# sap_flux-v20.net
KiCad netlist of a schematic drawn in EAGLE
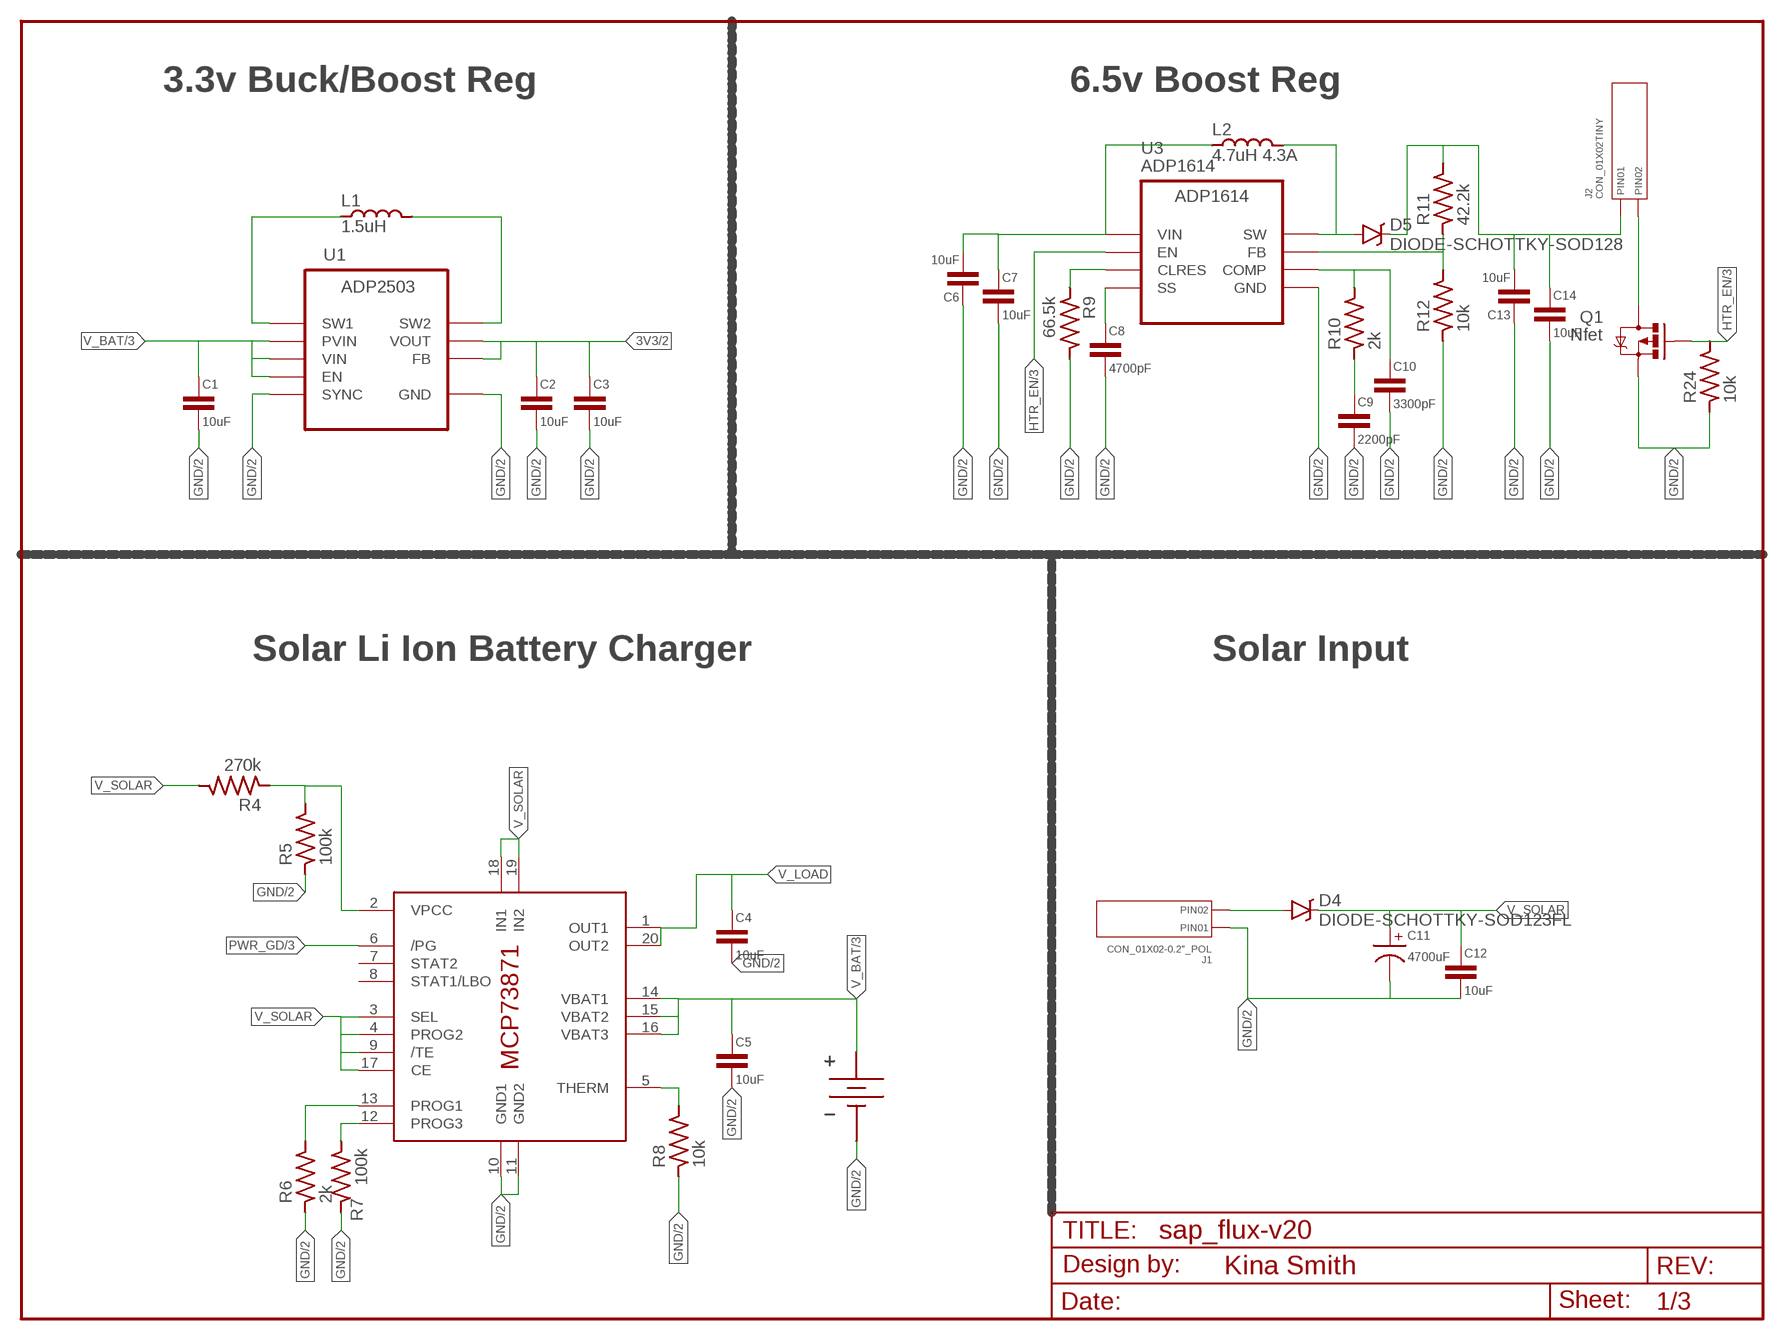
[diagram p0: schematic, sheet 1]
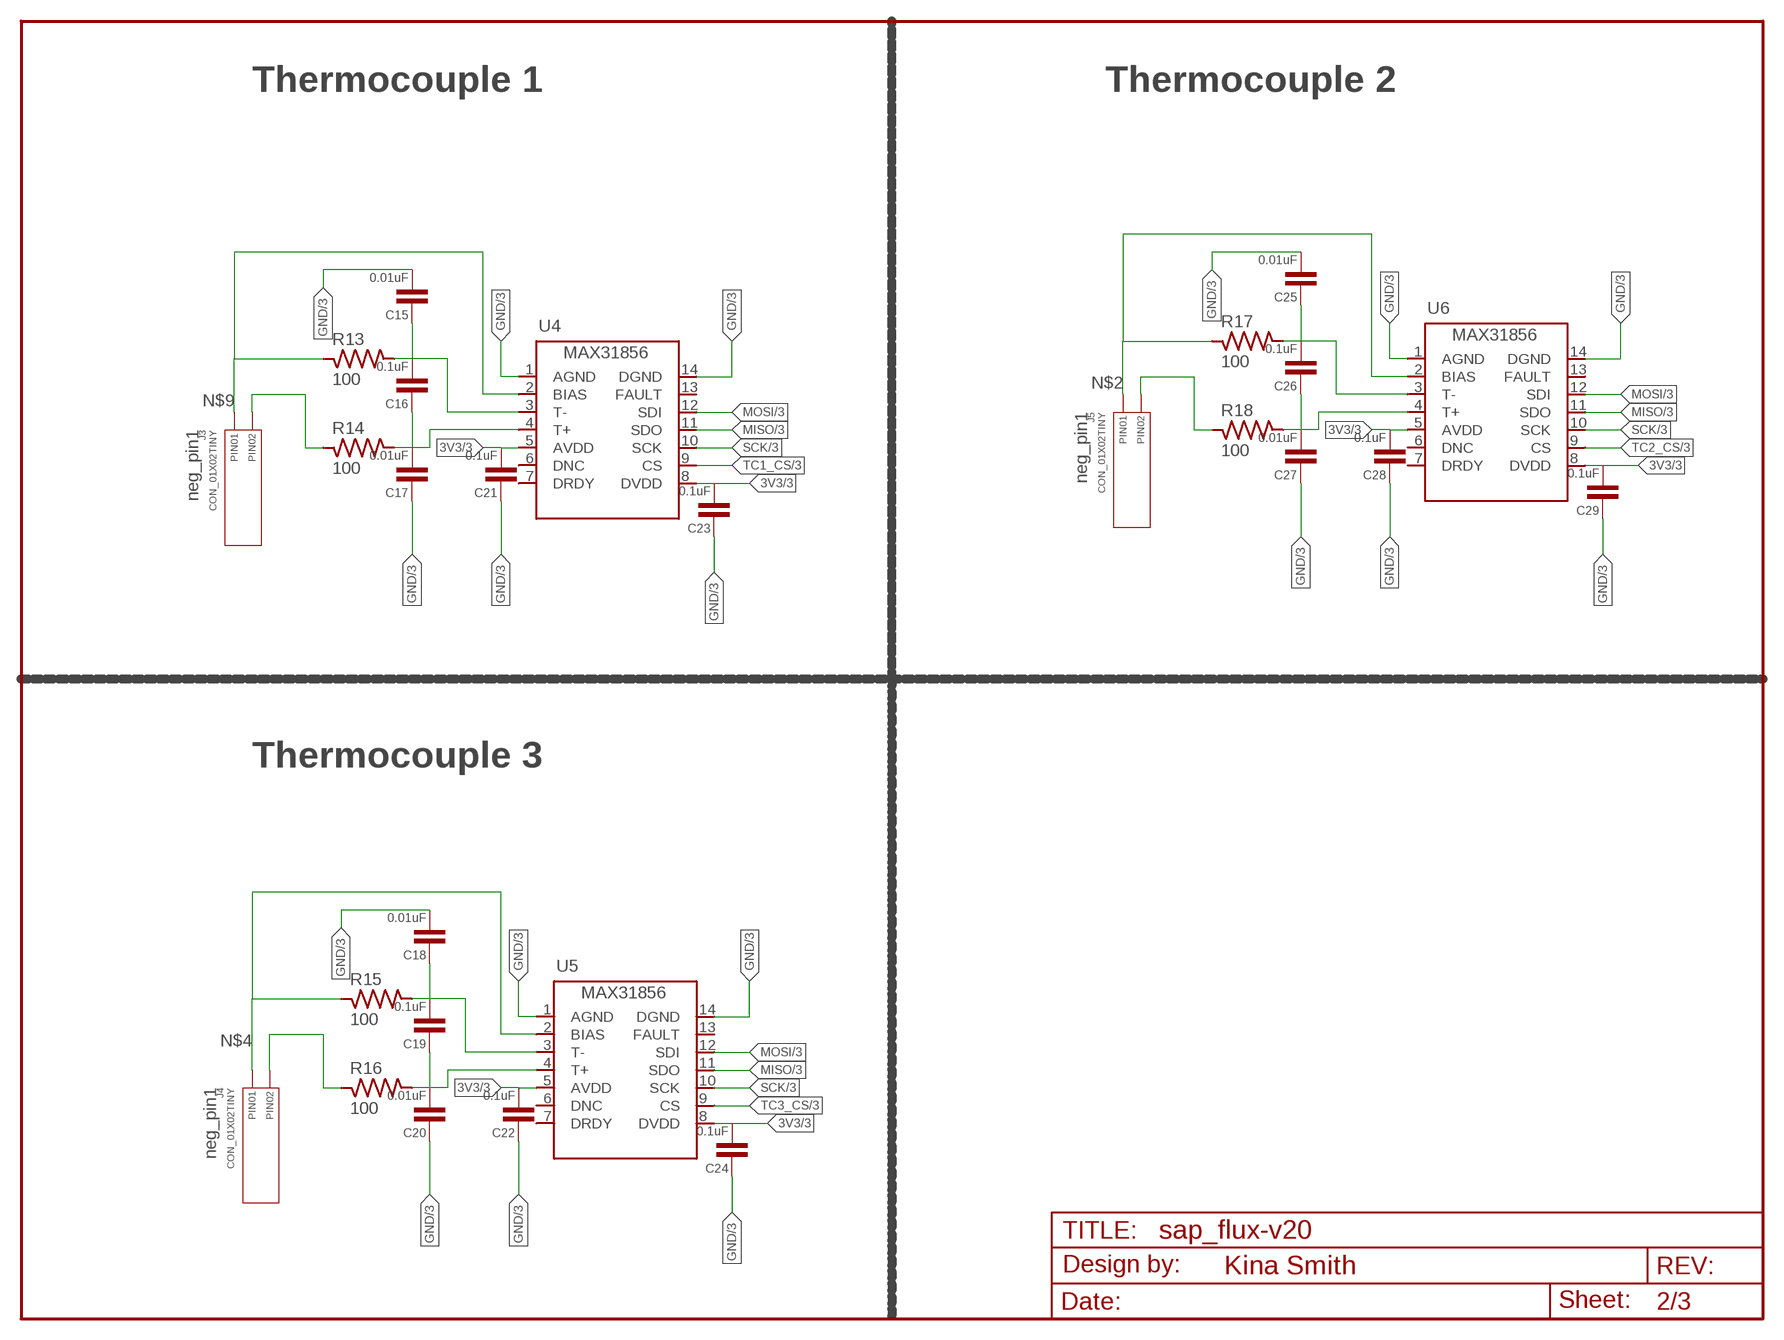
[diagram p1: schematic, sheet 2]
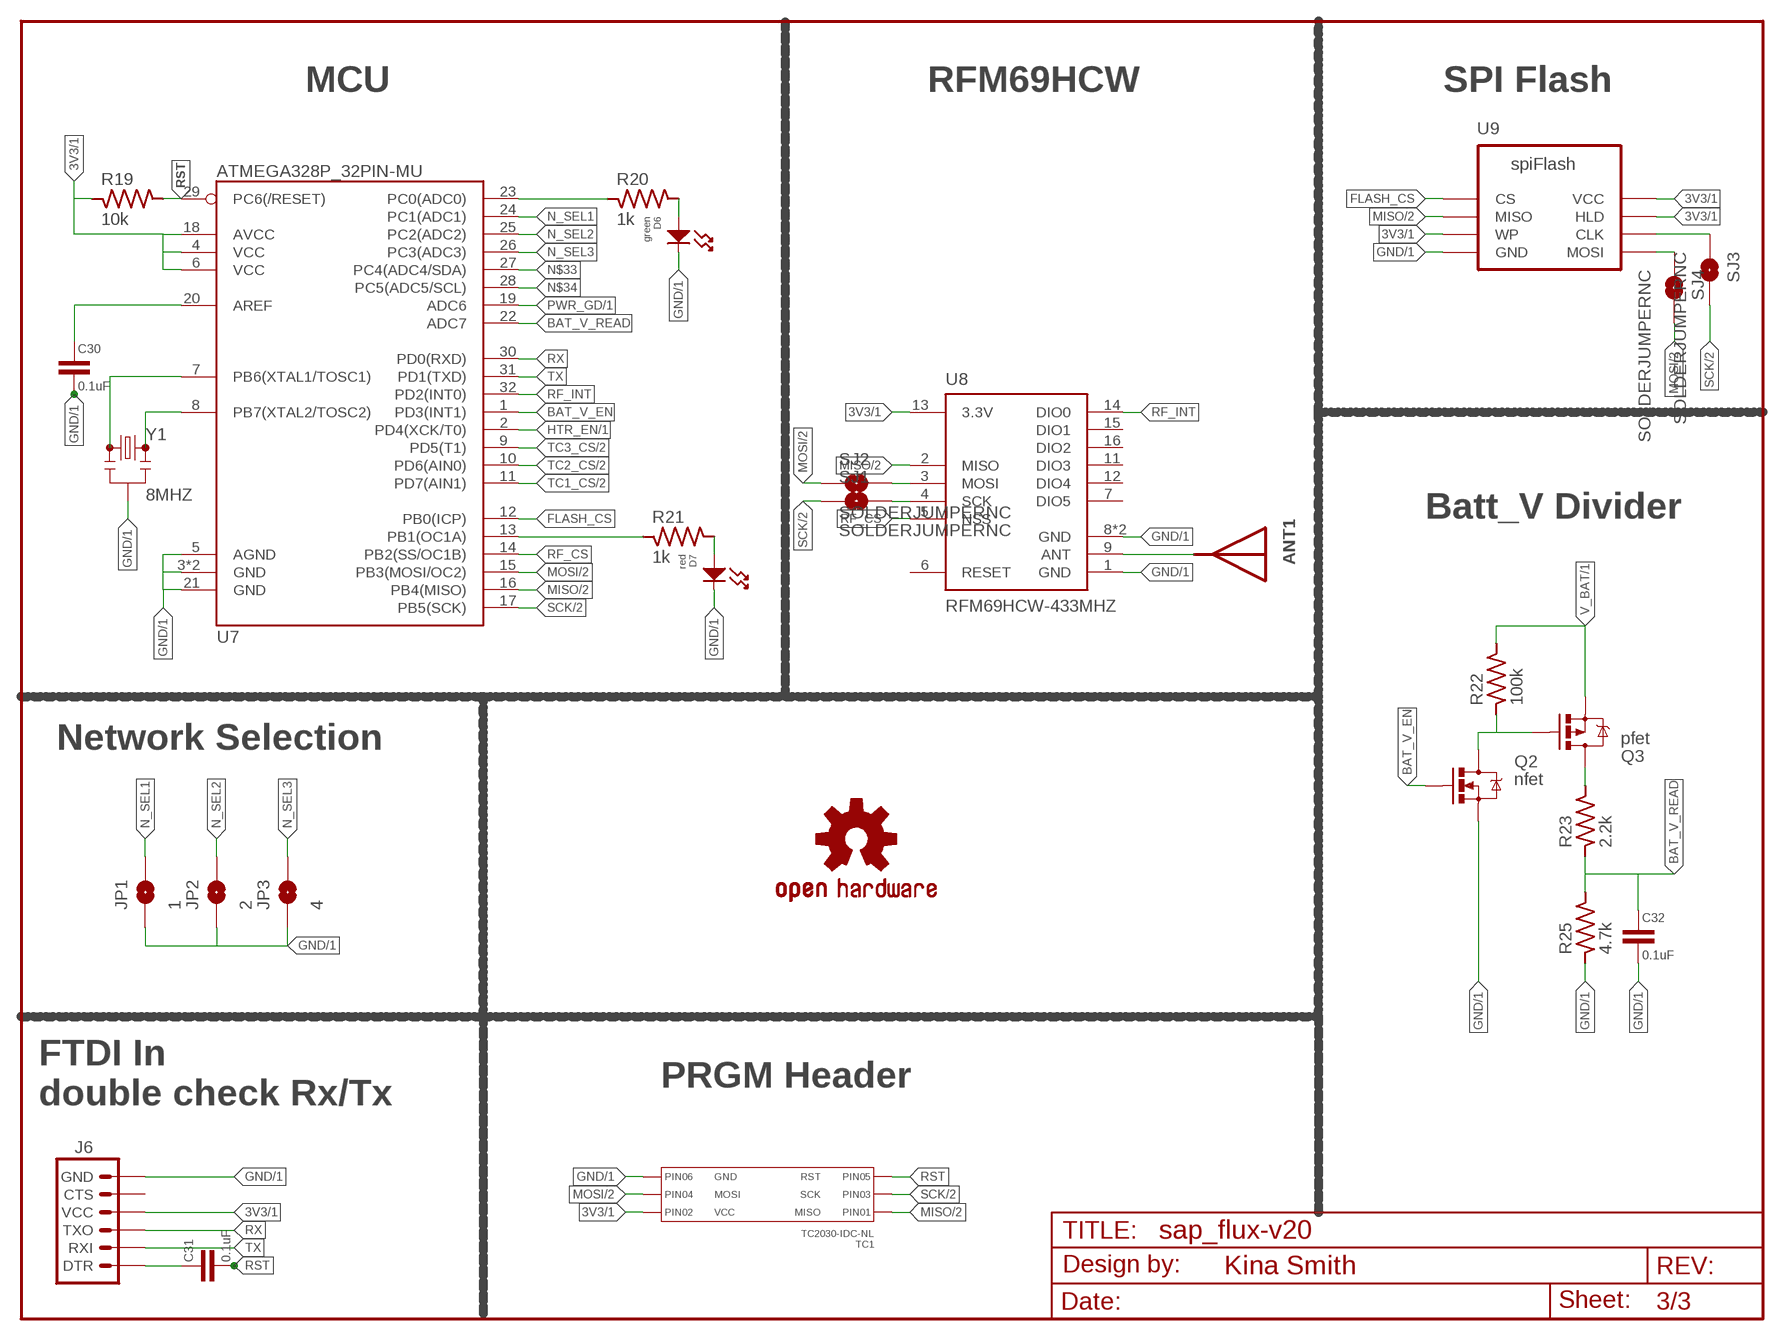
[diagram p2: schematic, sheet 3]

(export (version "E")
  (design (tool "Eeschema 10.0.6"))
  (components
    (comp (ref "ANT1")
      (value "ANTENNA-433_CHIP")
      (footprint "eagle-import:ANT_433_CHIP")
      (fields (field (name "PARTNO") "0433AT62A0020E"))
      (libsource (lib "eagle-import") (part "ANTENNA-433_CHIP"))
    )
    (comp (ref "C30")
      (value "0.1uF")
      (footprint "eagle-import:C0603-N")
      (fields (field (name "PARTNO") "CC0603KRX7R7BB104"))
      (libsource (lib "eagle-import") (part "CAPACITOR_NP0603-N"))
    )
    (comp (ref "C31")
      (value "0.1uF")
      (footprint "eagle-import:C0603-N")
      (fields (field (name "PARTNO") "CC0603KRX7R7BB104"))
      (libsource (lib "eagle-import") (part "CAPACITOR_NP0603-N"))
    )
    (comp (ref "C32")
      (value "0.1uF")
      (footprint "eagle-import:C0603-N")
      (fields (field (name "PARTNO") "CC0603KRX7R7BB104"))
      (libsource (lib "eagle-import") (part "CAPACITOR_NP0603-N"))
    )
    (comp (ref "D6")
      (value "green")
      (footprint "eagle-import:LED0603")
      (fields (field (name "HOUSEPART") "NO") (field (name "PARTNO") "LTST-C191KGKT"))
      (libsource (lib "eagle-import") (part "LED_SINGLE-0603"))
    )
    (comp (ref "D7")
      (value "red")
      (footprint "eagle-import:LED0603")
      (fields (field (name "HOUSEPART") "NO") (field (name "PARTNO") "LTST-C191KRKT"))
      (libsource (lib "eagle-import") (part "LED_SINGLE-0603"))
    )
    (comp (ref "FRAME3")
      (value "FRAME-LETTERNO_PACKAGE")
      (footprint "eagle-import:DUMMY")
      (fields (field (name "PARTNO") "NA") (field (name "DESIGNER") "Nobody"))
      (libsource (lib "eagle-import") (part "FRAME-LETTERNO_PACKAGE"))
    )
    (comp (ref "J6")
      (value "ARDUINO_SERIAL_PROGRAMPTH")
      (footprint "eagle-import:1X06")
      (fields (field (name "PARTNO") "68001-106HLF"))
      (libsource (lib "eagle-import") (part "ARDUINO_SERIAL_PROGRAMPTH"))
    )
    (comp (ref "JP1")
      (value "1")
      (footprint "eagle-import:PAD-JUMPER-2-NO_YES_SILK")
      (fields (field (name "PARTNO") "NA"))
      (libsource (lib "eagle-import") (part "JUMPER-PAD-2-NOYES_SILK"))
    )
    (comp (ref "JP2")
      (value "2")
      (footprint "eagle-import:PAD-JUMPER-2-NO_YES_SILK")
      (fields (field (name "PARTNO") "NA"))
      (libsource (lib "eagle-import") (part "JUMPER-PAD-2-NOYES_SILK"))
    )
    (comp (ref "JP3")
      (value "4")
      (footprint "eagle-import:PAD-JUMPER-2-NO_YES_SILK")
      (fields (field (name "PARTNO") "NA"))
      (libsource (lib "eagle-import") (part "JUMPER-PAD-2-NOYES_SILK"))
    )
    (comp (ref "LOGO1")
      (value "OSHW-LOGOS-COPPER")
      (footprint "eagle-import:OSHW-LOGO-S_COPPER")
      (libsource (lib "eagle-import") (part "OSHW-LOGOS-COPPER"))
    )
    (comp (ref "Q2")
      (value "nfet")
      (footprint "eagle-import:SOT23-3")
      (fields (field (name "PARTNO") "BSS138"))
      (libsource (lib "eagle-import") (part "MOSFET-NCHANNELSOT23-3"))
    )
    (comp (ref "Q3")
      (value "pfet")
      (footprint "eagle-import:SOT23-3")
      (fields (field (name "PARTNO") "IRLML2244TRPBF"))
      (libsource (lib "eagle-import") (part "MOSFET-PCHANNELSOT23-3"))
    )
    (comp (ref "R19")
      (value "10k")
      (footprint "eagle-import:R0603-N")
      (fields (field (name "PARTNO") "RC0603FR-0710KL"))
      (libsource (lib "eagle-import") (part "RESISTOR0603-N"))
    )
    (comp (ref "R20")
      (value "1k")
      (footprint "eagle-import:R0603-N")
      (fields (field (name "PARTNO") "RC0603FR-071KL"))
      (libsource (lib "eagle-import") (part "RESISTOR0603-N"))
    )
    (comp (ref "R21")
      (value "1k")
      (footprint "eagle-import:R0603-N")
      (fields (field (name "PARTNO") "RC0603FR-071KL"))
      (libsource (lib "eagle-import") (part "RESISTOR0603-N"))
    )
    (comp (ref "R22")
      (value "100k")
      (footprint "eagle-import:R0603-N")
      (fields (field (name "PARTNO") "RC0603FR-07100KL"))
      (libsource (lib "eagle-import") (part "RESISTOR0603-N"))
    )
    (comp (ref "R23")
      (value "2.2k")
      (footprint "eagle-import:R0603-N")
      (fields (field (name "PARTNO") "RC0603FR-072K2L"))
      (libsource (lib "eagle-import") (part "RESISTOR0603-N"))
    )
    (comp (ref "R25")
      (value "4.7k")
      (footprint "eagle-import:R0603-N")
      (fields (field (name "PARTNO") "RC0603FR-074K7L"))
      (libsource (lib "eagle-import") (part "RESISTOR0603-N"))
    )
    (comp (ref "SJ1")
      (value "SOLDERJUMPERNC")
      (footprint "eagle-import:SJ_2S")
      (fields (field (name "PARTNO") "NA"))
      (libsource (lib "eagle-import") (part "SOLDERJUMPERNC"))
    )
    (comp (ref "SJ2")
      (value "SOLDERJUMPERNC")
      (footprint "eagle-import:SJ_2S")
      (fields (field (name "PARTNO") "NA"))
      (libsource (lib "eagle-import") (part "SOLDERJUMPERNC"))
    )
    (comp (ref "SJ3")
      (value "SOLDERJUMPERNC")
      (footprint "eagle-import:SJ_2S")
      (fields (field (name "PARTNO") "NA"))
      (libsource (lib "eagle-import") (part "SOLDERJUMPERNC"))
    )
    (comp (ref "SJ4")
      (value "SOLDERJUMPERNC")
      (footprint "eagle-import:SJ_2S")
      (fields (field (name "PARTNO") "NA"))
      (libsource (lib "eagle-import") (part "SOLDERJUMPERNC"))
    )
    (comp (ref "TC1")
      (value "TC2030-IDC-NL")
      (footprint "eagle-import:TC2030-IDC-NL")
      (fields (field (name "HOUSEPART") "NO") (field (name "PARTNO") "NA"))
      (libsource (lib "eagle-import") (part "CON_02X03_TC2030-IDC-NL_AVRISP"))
    )
    (comp (ref "U7")
      (value "ATMEGA328P_32PIN-MU")
      (footprint "eagle-import:MLF32_RECTPADS")
      (fields (field (name "PARTNO") "ATMEGA328P-MU"))
      (libsource (lib "eagle-import") (part "ATMEGA328P_32PIN-MU"))
    )
    (comp (ref "U8")
      (value "RFM69HCW-433MHZ")
      (footprint "eagle-import:RFM69HCW-XXXS2")
      (fields (field (name "PARTNO") "COM-13910"))
      (libsource (lib "eagle-import") (part "RFM69HCW-433MHZ"))
    )
    (comp (ref "U9")
      (value "WINBOND_FLASH_4MBIT-SOIC")
      (footprint "eagle-import:SOIC8")
      (fields (field (name "PARTNO") "W25X40CLSNIG"))
      (libsource (lib "eagle-import") (part "WINBOND_FLASH_4MBIT-SOIC"))
    )
    (comp (ref "Y1")
      (value "8MHZ")
      (footprint "eagle-import:RESONATOR-SMD")
      (fields (field (name "PARTNO") "CSTCE8M00G55-R0"))
      (libsource (lib "eagle-import") (part "RESONATOR8MHZ"))
    )
    (comp (ref "BATT1")
      (value "BATTERY_HOLDER-18650_CLIP")
      (footprint "eagle-import:BAT_18650_CLIP")
      (fields (field (name "PARTNO") "54"))
      (libsource (lib "eagle-import") (part "BATTERY_HOLDER-18650_CLIP"))
    )
    (comp (ref "C1")
      (value "10uF")
      (footprint "eagle-import:C0805-N")
      (fields (field (name "PARTNO") "GRM21BR61C106KE15K"))
      (libsource (lib "eagle-import") (part "CAPACITOR_NP0805-N"))
    )
    (comp (ref "C2")
      (value "10uF")
      (footprint "eagle-import:C0805-N")
      (fields (field (name "PARTNO") "GRM21BR61C106KE15K"))
      (libsource (lib "eagle-import") (part "CAPACITOR_NP0805-N"))
    )
    (comp (ref "C3")
      (value "10uF")
      (footprint "eagle-import:C0805-N")
      (fields (field (name "PARTNO") "GRM21BR61C106KE15K"))
      (libsource (lib "eagle-import") (part "CAPACITOR_NP0805-N"))
    )
    (comp (ref "C4")
      (value "10uF")
      (footprint "eagle-import:C0805-N")
      (fields (field (name "PARTNO") "GRM21BR61C106KE15K"))
      (libsource (lib "eagle-import") (part "CAPACITOR_NP0805-N"))
    )
    (comp (ref "C5")
      (value "10uF")
      (footprint "eagle-import:C0805-N")
      (fields (field (name "PARTNO") "GRM21BR61C106KE15K"))
      (libsource (lib "eagle-import") (part "CAPACITOR_NP0805-N"))
    )
    (comp (ref "C6")
      (value "10uF")
      (footprint "eagle-import:C0805-N")
      (fields (field (name "PARTNO") "GRM21BR61C106KE15K"))
      (libsource (lib "eagle-import") (part "CAPACITOR_NP0805-N"))
    )
    (comp (ref "C7")
      (value "10uF")
      (footprint "eagle-import:C0805-N")
      (fields (field (name "PARTNO") "GRM21BR61C106KE15K"))
      (libsource (lib "eagle-import") (part "CAPACITOR_NP0805-N"))
    )
    (comp (ref "C8")
      (value "4700pF")
      (footprint "eagle-import:C0603-N")
      (fields (field (name "PARTNO") "GRM188R71C472KA01D"))
      (libsource (lib "eagle-import") (part "CAPACITOR_NP0603-N"))
    )
    (comp (ref "C9")
      (value "2200pF")
      (footprint "eagle-import:C0603-N")
      (fields (field (name "PARTNO") "GRM188R71C222KA01D"))
      (libsource (lib "eagle-import") (part "CAPACITOR_NP0603-N"))
    )
    (comp (ref "C10")
      (value "3300pF")
      (footprint "eagle-import:C0603-N")
      (fields (field (name "PARTNO") "C0603C332K4RACTU"))
      (libsource (lib "eagle-import") (part "CAPACITOR_NP0603-N"))
    )
    (comp (ref "C11")
      (value "4700uF")
      (footprint "eagle-import:CP_TH_5MM")
      (fields (field (name "PARTNO") "ECA-1AM472"))
      (libsource (lib "eagle-import") (part "CAPACITOR_P-TH_5MM"))
    )
    (comp (ref "C12")
      (value "10uF")
      (footprint "eagle-import:C0805-N")
      (fields (field (name "PARTNO") "GRM21BR61C106KE15K"))
      (libsource (lib "eagle-import") (part "CAPACITOR_NP0805-N"))
    )
    (comp (ref "C13")
      (value "10uF")
      (footprint "eagle-import:C0805-N")
      (fields (field (name "PARTNO") "GRM21BR61C106KE15K"))
      (libsource (lib "eagle-import") (part "CAPACITOR_NP0805-N"))
    )
    (comp (ref "C14")
      (value "10uF")
      (footprint "eagle-import:C0805-N")
      (fields (field (name "PARTNO") "GRM21BR61C106KE15K"))
      (libsource (lib "eagle-import") (part "CAPACITOR_NP0805-N"))
    )
    (comp (ref "D4")
      (value "DIODE-SCHOTTKY-SOD123FL")
      (footprint "eagle-import:SOD-123FL")
      (fields (field (name "PARTNO") "MBR120VLSFT1G"))
      (libsource (lib "eagle-import") (part "DIODE-SCHOTTKY-SOD123FL"))
    )
    (comp (ref "D5")
      (value "DIODE-SCHOTTKY-SOD128")
      (footprint "eagle-import:SOD128")
      (fields (field (name "PARTNO") "CMS05(TE12L,Q,M)"))
      (libsource (lib "eagle-import") (part "DIODE-SCHOTTKY-SOD128"))
    )
    (comp (ref "FRAME1")
      (value "FRAME-LETTER")
      (footprint "eagle-import:CREATIVE_COMMONS")
      (fields (field (name "PARTNO") "NA"))
      (libsource (lib "eagle-import") (part "FRAME-LETTER"))
    )
    (comp (ref "J1")
      (value "CON_01X02-0.2\"_POL")
      (footprint "eagle-import:1X02_SCREWTERM_0.2IN")
      (fields (field (name "PARTNO") "0398890042"))
      (libsource (lib "eagle-import") (part "CON_01X02-0.2{dblquote}_POL"))
    )
    (comp (ref "J2")
      (value "CON_01X02TINY")
      (footprint "eagle-import:1X02_TINY")
      (libsource (lib "eagle-import") (part "CON_01X02TINY"))
    )
    (comp (ref "L1")
      (value "1.5uH")
      (footprint "eagle-import:L3030")
      (fields (field (name "PARTNO") "NR3015T1R5N"))
      (libsource (lib "eagle-import") (part "INDUCTOR3030"))
    )
    (comp (ref "L2")
      (value "4.7uH 4.3A")
      (footprint "eagle-import:L8080")
      (fields (field (name "PARTNO") "NRS8040T100MJGJ"))
      (libsource (lib "eagle-import") (part "INDUCTOR8080"))
    )
    (comp (ref "Q1")
      (value "Nfet")
      (footprint "eagle-import:SOT23-3")
      (fields (field (name "PARTNO") "DMN2075U-7"))
      (libsource (lib "eagle-import") (part "MOSFET-PCHANNELSOT23-3"))
    )
    (comp (ref "R4")
      (value "270k")
      (footprint "eagle-import:R0603-N")
      (fields (field (name "PARTNO") "RC0603FR-07270KL"))
      (libsource (lib "eagle-import") (part "RESISTOR0603-N"))
    )
    (comp (ref "R5")
      (value "100k")
      (footprint "eagle-import:R0603-N")
      (fields (field (name "PARTNO") "RC0603FR-07100KL"))
      (libsource (lib "eagle-import") (part "RESISTOR0603-N"))
    )
    (comp (ref "R6")
      (value "2k")
      (footprint "eagle-import:R0603-N")
      (fields (field (name "PARTNO") "RC0603FR-072KL"))
      (libsource (lib "eagle-import") (part "RESISTOR0603-N"))
    )
    (comp (ref "R7")
      (value "100k")
      (footprint "eagle-import:R0603-N")
      (fields (field (name "PARTNO") "RC0603FR-07100KL"))
      (libsource (lib "eagle-import") (part "RESISTOR0603-N"))
    )
    (comp (ref "R8")
      (value "10k")
      (footprint "eagle-import:R0603-N")
      (fields (field (name "PARTNO") "RC0603FR-0710KL"))
      (libsource (lib "eagle-import") (part "RESISTOR0603-N"))
    )
    (comp (ref "R9")
      (value "66.5k")
      (footprint "eagle-import:R0603-N")
      (fields (field (name "PARTNO") "RC0603FR-0766K5L"))
      (libsource (lib "eagle-import") (part "RESISTOR0603-N"))
    )
    (comp (ref "R10")
      (value "2k")
      (footprint "eagle-import:R0603-N")
      (fields (field (name "PARTNO") "RC0603FR-072KL"))
      (libsource (lib "eagle-import") (part "RESISTOR0603-N"))
    )
    (comp (ref "R11")
      (value "42.2k")
      (footprint "eagle-import:R0603-N")
      (fields (field (name "PARTNO") "RC0603FR-0742K2L"))
      (libsource (lib "eagle-import") (part "RESISTOR0603-N"))
    )
    (comp (ref "R12")
      (value "10k")
      (footprint "eagle-import:R0603-N")
      (fields (field (name "PARTNO") "RC0603FR-0710KL"))
      (libsource (lib "eagle-import") (part "RESISTOR0603-N"))
    )
    (comp (ref "R24")
      (value "10k")
      (footprint "eagle-import:R0603-N")
      (fields (field (name "PARTNO") "RC0603FR-0710KL"))
      (libsource (lib "eagle-import") (part "RESISTOR0603-N"))
    )
    (comp (ref "U1")
      (value "ADP2503")
      (footprint "eagle-import:DFN300X300X80-11N")
      (fields (field (name "PARTNO") "ADP2503ACPZ-3.3-R7 ") (field (name "PARTNO_1") "ADP2503ACPZ-3.3-R7"))
      (libsource (lib "eagle-import") (part "ADP2503"))
    )
    (comp (ref "U2")
      (value "MCP73871")
      (footprint "eagle-import:QFN20")
      (fields (field (name "PARTNO") "MCP73871-2AAI/ML-ND"))
      (libsource (lib "eagle-import") (part "MCP73871"))
    )
    (comp (ref "U3")
      (value "ADP1614")
      (footprint "eagle-import:DFN300X300X80-11N")
      (fields (field (name "PARTNO") "ADP1614ACPZ-R7") (field (name "PARTNO_1") "ADP1614ACPZ-650-R7"))
      (libsource (lib "eagle-import") (part "ADP1614"))
    )
    (comp (ref "C15")
      (value "0.01uF")
      (footprint "eagle-import:C0603-N")
      (fields (field (name "PARTNO") "GRM188R71C103KA01D"))
      (libsource (lib "eagle-import") (part "CAPACITOR_NP0603-N"))
    )
    (comp (ref "C16")
      (value "0.1uF")
      (footprint "eagle-import:C0603-N")
      (fields (field (name "PARTNO") "CC0603KRX7R7BB104"))
      (libsource (lib "eagle-import") (part "CAPACITOR_NP0603-N"))
    )
    (comp (ref "C17")
      (value "0.01uF")
      (footprint "eagle-import:C0603-N")
      (fields (field (name "PARTNO") "GRM188R71C103KA01D"))
      (libsource (lib "eagle-import") (part "CAPACITOR_NP0603-N"))
    )
    (comp (ref "C18")
      (value "0.01uF")
      (footprint "eagle-import:C0603-N")
      (fields (field (name "PARTNO") "GRM188R71C103KA01D"))
      (libsource (lib "eagle-import") (part "CAPACITOR_NP0603-N"))
    )
    (comp (ref "C19")
      (value "0.1uF")
      (footprint "eagle-import:C0603-N")
      (fields (field (name "PARTNO") "CC0603KRX7R7BB104"))
      (libsource (lib "eagle-import") (part "CAPACITOR_NP0603-N"))
    )
    (comp (ref "C20")
      (value "0.01uF")
      (footprint "eagle-import:C0603-N")
      (fields (field (name "PARTNO") "GRM188R71C103KA01D"))
      (libsource (lib "eagle-import") (part "CAPACITOR_NP0603-N"))
    )
    (comp (ref "C21")
      (value "0.1uF")
      (footprint "eagle-import:C0603-N")
      (fields (field (name "PARTNO") "CC0603KRX7R7BB104"))
      (libsource (lib "eagle-import") (part "CAPACITOR_NP0603-N"))
    )
    (comp (ref "C22")
      (value "0.1uF")
      (footprint "eagle-import:C0603-N")
      (fields (field (name "PARTNO") "CC0603KRX7R7BB104"))
      (libsource (lib "eagle-import") (part "CAPACITOR_NP0603-N"))
    )
    (comp (ref "C23")
      (value "0.1uF")
      (footprint "eagle-import:C0603-N")
      (fields (field (name "PARTNO") "CC0603KRX7R7BB104"))
      (libsource (lib "eagle-import") (part "CAPACITOR_NP0603-N"))
    )
    (comp (ref "C24")
      (value "0.1uF")
      (footprint "eagle-import:C0603-N")
      (fields (field (name "PARTNO") "CC0603KRX7R7BB104"))
      (libsource (lib "eagle-import") (part "CAPACITOR_NP0603-N"))
    )
    (comp (ref "C25")
      (value "0.01uF")
      (footprint "eagle-import:C0603-N")
      (fields (field (name "PARTNO") "GRM188R71C103KA01D"))
      (libsource (lib "eagle-import") (part "CAPACITOR_NP0603-N"))
    )
    (comp (ref "C26")
      (value "0.1uF")
      (footprint "eagle-import:C0603-N")
      (fields (field (name "PARTNO") "CC0603KRX7R7BB104"))
      (libsource (lib "eagle-import") (part "CAPACITOR_NP0603-N"))
    )
    (comp (ref "C27")
      (value "0.01uF")
      (footprint "eagle-import:C0603-N")
      (fields (field (name "PARTNO") "GRM188R71C103KA01D"))
      (libsource (lib "eagle-import") (part "CAPACITOR_NP0603-N"))
    )
    (comp (ref "C28")
      (value "0.1uF")
      (footprint "eagle-import:C0603-N")
      (fields (field (name "PARTNO") "CC0603KRX7R7BB104"))
      (libsource (lib "eagle-import") (part "CAPACITOR_NP0603-N"))
    )
    (comp (ref "C29")
      (value "0.1uF")
      (footprint "eagle-import:C0603-N")
      (fields (field (name "PARTNO") "CC0603KRX7R7BB104"))
      (libsource (lib "eagle-import") (part "CAPACITOR_NP0603-N"))
    )
    (comp (ref "FRAME2")
      (value "FRAME-LETTERNO_PACKAGE")
      (footprint "eagle-import:DUMMY")
      (fields (field (name "PARTNO") "NA") (field (name "DESIGNER") "Nobody"))
      (libsource (lib "eagle-import") (part "FRAME-LETTERNO_PACKAGE"))
    )
    (comp (ref "J3")
      (value "CON_01X02TINY")
      (footprint "eagle-import:1X02_TINY")
      (fields (field (name "NOTE") "neg_pin1"))
      (libsource (lib "eagle-import") (part "CON_01X02TINY"))
    )
    (comp (ref "J4")
      (value "CON_01X02TINY")
      (footprint "eagle-import:1X02_TINY")
      (fields (field (name "NOTE") "neg_pin1"))
      (libsource (lib "eagle-import") (part "CON_01X02TINY"))
    )
    (comp (ref "J5")
      (value "CON_01X02TINY")
      (footprint "eagle-import:1X02_TINY")
      (fields (field (name "NOTE") "neg_pin1"))
      (libsource (lib "eagle-import") (part "CON_01X02TINY"))
    )
    (comp (ref "R13")
      (value "100")
      (footprint "eagle-import:R0603-N")
      (fields (field (name "PARTNO") "RC0603FR-07100RL"))
      (libsource (lib "eagle-import") (part "RESISTOR0603-N"))
    )
    (comp (ref "R14")
      (value "100")
      (footprint "eagle-import:R0603-N")
      (fields (field (name "PARTNO") "RC0603FR-07100RL"))
      (libsource (lib "eagle-import") (part "RESISTOR0603-N"))
    )
    (comp (ref "R15")
      (value "100")
      (footprint "eagle-import:R0603-N")
      (fields (field (name "PARTNO") "RC0603FR-07100RL"))
      (libsource (lib "eagle-import") (part "RESISTOR0603-N"))
    )
    (comp (ref "R16")
      (value "100")
      (footprint "eagle-import:R0603-N")
      (fields (field (name "PARTNO") "RC0603FR-07100RL"))
      (libsource (lib "eagle-import") (part "RESISTOR0603-N"))
    )
    (comp (ref "R17")
      (value "100")
      (footprint "eagle-import:R0603-N")
      (fields (field (name "PARTNO") "RC0603FR-07100RL"))
      (libsource (lib "eagle-import") (part "RESISTOR0603-N"))
    )
    (comp (ref "R18")
      (value "100")
      (footprint "eagle-import:R0603-N")
      (fields (field (name "PARTNO") "RC0603FR-07100RL"))
      (libsource (lib "eagle-import") (part "RESISTOR0603-N"))
    )
    (comp (ref "U4")
      (value "MAX31856MUD+")
      (footprint "eagle-import:TSSOP14")
      (libsource (lib "eagle-import") (part "MAX31856MUD+"))
    )
    (comp (ref "U5")
      (value "MAX31856MUD+")
      (footprint "eagle-import:TSSOP14")
      (libsource (lib "eagle-import") (part "MAX31856MUD+"))
    )
    (comp (ref "U6")
      (value "MAX31856MUD+")
      (footprint "eagle-import:TSSOP14")
      (libsource (lib "eagle-import") (part "MAX31856MUD+"))
    )
  )
  (nets
    (net (code "1") (name "3V3") (class "Default")
      (node (ref "C2") (pin "1") (pinfunction "1_1") (pintype "passive"))
      (node (ref "C21") (pin "2") (pinfunction "2_2") (pintype "passive"))
      (node (ref "C22") (pin "2") (pinfunction "2_2") (pintype "passive"))
      (node (ref "C23") (pin "2") (pinfunction "2_2") (pintype "passive"))
      (node (ref "C24") (pin "2") (pinfunction "2_2") (pintype "passive"))
      (node (ref "C28") (pin "2") (pinfunction "2_2") (pintype "passive"))
      (node (ref "C29") (pin "2") (pinfunction "2_2") (pintype "passive"))
      (node (ref "C3") (pin "1") (pinfunction "1_1") (pintype "passive"))
      (node (ref "J6") (pin "4") (pinfunction "VCC_4") (pintype "passive"))
      (node (ref "R19") (pin "1") (pinfunction "P$1_1") (pintype "passive"))
      (node (ref "TC1") (pin "P$2") (pinfunction "PIN2_P$2") (pintype "bidirectional"))
      (node (ref "U1") (pin "1") (pinfunction "VOUT_1") (pintype "bidirectional"))
      (node (ref "U1") (pin "10") (pinfunction "FB_10") (pintype "bidirectional"))
      (node (ref "U4") (pin "5") (pinfunction "AVDD_5") (pintype "bidirectional"))
      (node (ref "U4") (pin "8") (pinfunction "DVDD_8") (pintype "bidirectional"))
      (node (ref "U5") (pin "5") (pinfunction "AVDD_5") (pintype "bidirectional"))
      (node (ref "U5") (pin "8") (pinfunction "DVDD_8") (pintype "bidirectional"))
      (node (ref "U6") (pin "5") (pinfunction "AVDD_5") (pintype "bidirectional"))
      (node (ref "U6") (pin "8") (pinfunction "DVDD_8") (pintype "bidirectional"))
      (node (ref "U7") (pin "18") (pinfunction "AVCC_18") (pintype "bidirectional"))
      (node (ref "U7") (pin "4") (pinfunction "VCC_4") (pintype "bidirectional"))
      (node (ref "U7") (pin "6") (pinfunction "VCC_6") (pintype "bidirectional"))
      (node (ref "U8") (pin "13") (pinfunction "3.3V_13") (pintype "power_in"))
      (node (ref "U9") (pin "3") (pinfunction "WP_3") (pintype "bidirectional"))
      (node (ref "U9") (pin "7") (pinfunction "HLD_7") (pintype "bidirectional"))
      (node (ref "U9") (pin "8") (pinfunction "VCC_8") (pintype "bidirectional"))
    )
    (net (code "2") (name "BAT_V_EN") (class "Default")
      (node (ref "Q2") (pin "1") (pinfunction "G_1") (pintype "passive"))
      (node (ref "U7") (pin "1") (pinfunction "PD3(INT1)_1") (pintype "bidirectional"))
    )
    (net (code "3") (name "BAT_V_READ") (class "Default")
      (node (ref "C32") (pin "1") (pinfunction "1_1") (pintype "passive"))
      (node (ref "R23") (pin "1") (pinfunction "P$1_1") (pintype "passive"))
      (node (ref "R25") (pin "2") (pinfunction "P$2_2") (pintype "passive"))
      (node (ref "U7") (pin "22") (pinfunction "ADC7_22") (pintype "bidirectional"))
    )
    (net (code "4") (name "FLASH_CS") (class "Default")
      (node (ref "U7") (pin "12") (pinfunction "PB0(ICP)_12") (pintype "bidirectional"))
      (node (ref "U9") (pin "1") (pinfunction "CS_1") (pintype "bidirectional"))
    )
    (net (code "5") (name "GND") (class "Default")
      (node (ref "BATT1") (pin "NEG_1") (pinfunction "GND_NEG_1") (pintype "bidirectional"))
      (node (ref "BATT1") (pin "NEG_2") (pinfunction "GND_NEG_2") (pintype "bidirectional"))
      (node (ref "BATT1") (pin "NEG_3") (pinfunction "GND_NEG_3") (pintype "bidirectional"))
      (node (ref "C1") (pin "2") (pinfunction "2_2") (pintype "passive"))
      (node (ref "C10") (pin "2") (pinfunction "2_2") (pintype "passive"))
      (node (ref "C11") (pin "NEG") (pinfunction "NEG_NEG") (pintype "passive"))
      (node (ref "C12") (pin "2") (pinfunction "2_2") (pintype "passive"))
      (node (ref "C13") (pin "1") (pinfunction "1_1") (pintype "passive"))
      (node (ref "C14") (pin "2") (pinfunction "2_2") (pintype "passive"))
      (node (ref "C15") (pin "2") (pinfunction "2_2") (pintype "passive"))
      (node (ref "C17") (pin "1") (pinfunction "1_1") (pintype "passive"))
      (node (ref "C18") (pin "2") (pinfunction "2_2") (pintype "passive"))
      (node (ref "C2") (pin "2") (pinfunction "2_2") (pintype "passive"))
      (node (ref "C20") (pin "1") (pinfunction "1_1") (pintype "passive"))
      (node (ref "C21") (pin "1") (pinfunction "1_1") (pintype "passive"))
      (node (ref "C22") (pin "1") (pinfunction "1_1") (pintype "passive"))
      (node (ref "C23") (pin "1") (pinfunction "1_1") (pintype "passive"))
      (node (ref "C24") (pin "1") (pinfunction "1_1") (pintype "passive"))
      (node (ref "C25") (pin "2") (pinfunction "2_2") (pintype "passive"))
      (node (ref "C27") (pin "1") (pinfunction "1_1") (pintype "passive"))
      (node (ref "C28") (pin "1") (pinfunction "1_1") (pintype "passive"))
      (node (ref "C29") (pin "1") (pinfunction "1_1") (pintype "passive"))
      (node (ref "C3") (pin "2") (pinfunction "2_2") (pintype "passive"))
      (node (ref "C30") (pin "2") (pinfunction "2_2") (pintype "passive"))
      (node (ref "C32") (pin "2") (pinfunction "2_2") (pintype "passive"))
      (node (ref "C4") (pin "2") (pinfunction "2_2") (pintype "passive"))
      (node (ref "C5") (pin "2") (pinfunction "2_2") (pintype "passive"))
      (node (ref "C6") (pin "1") (pinfunction "1_1") (pintype "passive"))
      (node (ref "C7") (pin "2") (pinfunction "2_2") (pintype "passive"))
      (node (ref "C8") (pin "2") (pinfunction "2_2") (pintype "passive"))
      (node (ref "C9") (pin "2") (pinfunction "2_2") (pintype "passive"))
      (node (ref "D6") (pin "CATHODE") (pinfunction "CATHODE_CATHODE") (pintype "power_in"))
      (node (ref "D7") (pin "CATHODE") (pinfunction "CATHODE_CATHODE") (pintype "power_in"))
      (node (ref "J1") (pin "NEG") (pinfunction "PIN1_NEG") (pintype "bidirectional"))
      (node (ref "J6") (pin "6") (pinfunction "GND_6") (pintype "passive"))
      (node (ref "JP1") (pin "1") (pinfunction "1_1") (pintype "passive"))
      (node (ref "JP2") (pin "1") (pinfunction "1_1") (pintype "passive"))
      (node (ref "JP3") (pin "1") (pinfunction "1_1") (pintype "passive"))
      (node (ref "Q1") (pin "2") (pinfunction "S_2") (pintype "passive"))
      (node (ref "Q2") (pin "2") (pinfunction "S_2") (pintype "passive"))
      (node (ref "R12") (pin "1") (pinfunction "P$1_1") (pintype "passive"))
      (node (ref "R24") (pin "1") (pinfunction "P$1_1") (pintype "passive"))
      (node (ref "R25") (pin "1") (pinfunction "P$1_1") (pintype "passive"))
      (node (ref "R5") (pin "1") (pinfunction "P$1_1") (pintype "passive"))
      (node (ref "R6") (pin "1") (pinfunction "P$1_1") (pintype "passive"))
      (node (ref "R7") (pin "1") (pinfunction "P$1_1") (pintype "passive"))
      (node (ref "R8") (pin "1") (pinfunction "P$1_1") (pintype "passive"))
      (node (ref "R9") (pin "2") (pinfunction "P$2_2") (pintype "passive"))
      (node (ref "TC1") (pin "P$6") (pinfunction "PIN6_P$6") (pintype "bidirectional"))
      (node (ref "U1") (pin "11") (pinfunction "GND_11") (pintype "bidirectional"))
      (node (ref "U1") (pin "3") (pinfunction "GND_3") (pintype "bidirectional"))
      (node (ref "U1") (pin "7") (pinfunction "SYNC_7") (pintype "bidirectional"))
      (node (ref "U1") (pin "9") (pinfunction "GND_9") (pintype "bidirectional"))
      (node (ref "U2") (pin "10") (pinfunction "GND1_10") (pintype "power_in"))
      (node (ref "U2") (pin "11") (pinfunction "GND2_11") (pintype "power_in"))
      (node (ref "U3") (pin "11") (pinfunction "GND_11") (pintype "bidirectional"))
      (node (ref "U3") (pin "4") (pinfunction "GND_4") (pintype "bidirectional"))
      (node (ref "U3") (pin "5") (pinfunction "GND_5") (pintype "bidirectional"))
      (node (ref "U4") (pin "1") (pinfunction "AGND_1") (pintype "bidirectional"))
      (node (ref "U4") (pin "14") (pinfunction "DGND_14") (pintype "bidirectional"))
      (node (ref "U5") (pin "1") (pinfunction "AGND_1") (pintype "bidirectional"))
      (node (ref "U5") (pin "14") (pinfunction "DGND_14") (pintype "bidirectional"))
      (node (ref "U6") (pin "1") (pinfunction "AGND_1") (pintype "bidirectional"))
      (node (ref "U6") (pin "14") (pinfunction "DGND_14") (pintype "bidirectional"))
      (node (ref "U7") (pin "21") (pinfunction "GND_21") (pintype "bidirectional"))
      (node (ref "U7") (pin "3") (pinfunction "GND_3") (pintype "bidirectional"))
      (node (ref "U7") (pin "5") (pinfunction "AGND_5") (pintype "bidirectional"))
      (node (ref "U7") (pin "PAD") (pinfunction "GND_PAD") (pintype "bidirectional"))
      (node (ref "U8") (pin "1") (pinfunction "GND_1") (pintype "power_in"))
      (node (ref "U8") (pin "10") (pinfunction "GND_10") (pintype "power_in"))
      (node (ref "U8") (pin "8") (pinfunction "GND_8") (pintype "power_in"))
      (node (ref "U9") (pin "4") (pinfunction "GND_4") (pintype "bidirectional"))
      (node (ref "Y1") (pin "2") (pinfunction "2_2") (pintype "passive"))
    )
    (net (code "6") (name "HTR_EN") (class "Default")
      (node (ref "Q1") (pin "1") (pinfunction "G_1") (pintype "passive"))
      (node (ref "R24") (pin "2") (pinfunction "P$2_2") (pintype "passive"))
      (node (ref "U3") (pin "3") (pinfunction "EN_3") (pintype "bidirectional"))
      (node (ref "U7") (pin "2") (pinfunction "PD4(XCK/T0)_2") (pintype "bidirectional"))
    )
    (net (code "7") (name "MISO") (class "Default")
      (node (ref "TC1") (pin "P$1") (pinfunction "PIN1_P$1") (pintype "bidirectional"))
      (node (ref "U4") (pin "11") (pinfunction "SDO_11") (pintype "bidirectional"))
      (node (ref "U5") (pin "11") (pinfunction "SDO_11") (pintype "bidirectional"))
      (node (ref "U6") (pin "11") (pinfunction "SDO_11") (pintype "bidirectional"))
      (node (ref "U7") (pin "16") (pinfunction "PB4(MISO)_16") (pintype "bidirectional"))
      (node (ref "U8") (pin "2") (pinfunction "MISO_2") (pintype "bidirectional"))
      (node (ref "U9") (pin "2") (pinfunction "MISO_2") (pintype "bidirectional"))
    )
    (net (code "8") (name "MOSI") (class "Default")
      (node (ref "SJ2") (pin "1") (pinfunction "1_1") (pintype "passive"))
      (node (ref "SJ4") (pin "2") (pinfunction "2_2") (pintype "passive"))
      (node (ref "TC1") (pin "P$4") (pinfunction "PIN4_P$4") (pintype "bidirectional"))
      (node (ref "U4") (pin "12") (pinfunction "SDI_12") (pintype "bidirectional"))
      (node (ref "U5") (pin "12") (pinfunction "SDI_12") (pintype "bidirectional"))
      (node (ref "U6") (pin "12") (pinfunction "SDI_12") (pintype "bidirectional"))
      (node (ref "U7") (pin "15") (pinfunction "PB3(MOSI/OC2)_15") (pintype "bidirectional"))
    )
    (net (code "9") (name "N$2") (class "Default")
      (node (ref "J5") (pin "NEG") (pinfunction "PIN1_NEG") (pintype "bidirectional"))
      (node (ref "R17") (pin "1") (pinfunction "P$1_1") (pintype "passive"))
      (node (ref "U6") (pin "2") (pinfunction "BIAS_2") (pintype "bidirectional"))
    )
    (net (code "10") (name "N$4") (class "Default")
      (node (ref "J4") (pin "NEG") (pinfunction "PIN1_NEG") (pintype "bidirectional"))
      (node (ref "R15") (pin "1") (pinfunction "P$1_1") (pintype "passive"))
      (node (ref "U5") (pin "2") (pinfunction "BIAS_2") (pintype "bidirectional"))
    )
    (net (code "11") (name "N$9") (class "Default")
      (node (ref "J3") (pin "NEG") (pinfunction "PIN1_NEG") (pintype "bidirectional"))
      (node (ref "R13") (pin "1") (pinfunction "P$1_1") (pintype "passive"))
      (node (ref "U4") (pin "2") (pinfunction "BIAS_2") (pintype "bidirectional"))
    )
    (net (code "12") (name "N$33") (class "Default")
      (node (ref "U7") (pin "27") (pinfunction "PC4(ADC4/SDA)_27") (pintype "bidirectional"))
    )
    (net (code "13") (name "N$34") (class "Default")
      (node (ref "U7") (pin "28") (pinfunction "PC5(ADC5/SCL)_28") (pintype "bidirectional"))
    )
    (net (code "14") (name "N_SEL1") (class "Default")
      (node (ref "JP1") (pin "2") (pinfunction "2_2") (pintype "passive"))
      (node (ref "U7") (pin "24") (pinfunction "PC1(ADC1)_24") (pintype "bidirectional"))
    )
    (net (code "15") (name "N_SEL2") (class "Default")
      (node (ref "JP2") (pin "2") (pinfunction "2_2") (pintype "passive"))
      (node (ref "U7") (pin "25") (pinfunction "PC2(ADC2)_25") (pintype "bidirectional"))
    )
    (net (code "16") (name "N_SEL3") (class "Default")
      (node (ref "JP3") (pin "2") (pinfunction "2_2") (pintype "passive"))
      (node (ref "U7") (pin "26") (pinfunction "PC3(ADC3)_26") (pintype "bidirectional"))
    )
    (net (code "17") (name "Net-(D5-A)") (class "Default")
      (node (ref "D5") (pin "A-2") (pinfunction "A_A-2") (pintype "passive"))
      (node (ref "L2") (pin "2") (pinfunction "P$2_2") (pintype "passive"))
      (node (ref "U3") (pin "6") (pinfunction "SW_6") (pintype "bidirectional"))
      (node (ref "U3") (pin "7") (pinfunction "SW_7") (pintype "bidirectional"))
    )
    (net (code "18") (name "Net-(D5-C)") (class "Default")
      (node (ref "C13") (pin "2") (pinfunction "2_2") (pintype "passive"))
      (node (ref "C14") (pin "1") (pinfunction "1_1") (pintype "passive"))
      (node (ref "D5") (pin "C-1") (pinfunction "C_C-1") (pintype "passive"))
      (node (ref "J2") (pin "NEG") (pinfunction "PIN1_NEG") (pintype "bidirectional"))
      (node (ref "R11") (pin "2") (pinfunction "P$2_2") (pintype "passive"))
    )
    (net (code "19") (name "Net-(J1-PIN2)") (class "Default")
      (node (ref "D4") (pin "A") (pinfunction "A_A") (pintype "passive"))
      (node (ref "J1") (pin "POS") (pinfunction "PIN2_POS") (pintype "bidirectional"))
    )
    (net (code "20") (name "Net-(J2-PIN2)") (class "Default")
      (node (ref "J2") (pin "POS") (pinfunction "PIN2_POS") (pintype "bidirectional"))
      (node (ref "Q1") (pin "3") (pinfunction "D_3") (pintype "passive"))
    )
    (net (code "21") (name "Net-(J3-PIN2)") (class "Default")
      (node (ref "J3") (pin "POS") (pinfunction "PIN2_POS") (pintype "bidirectional"))
      (node (ref "R14") (pin "1") (pinfunction "P$1_1") (pintype "passive"))
    )
    (net (code "22") (name "Net-(J4-PIN2)") (class "Default")
      (node (ref "J4") (pin "POS") (pinfunction "PIN2_POS") (pintype "bidirectional"))
      (node (ref "R16") (pin "1") (pinfunction "P$1_1") (pintype "passive"))
    )
    (net (code "23") (name "Net-(J5-PIN2)") (class "Default")
      (node (ref "J5") (pin "POS") (pinfunction "PIN2_POS") (pintype "bidirectional"))
      (node (ref "R18") (pin "1") (pinfunction "P$1_1") (pintype "passive"))
    )
    (net (code "24") (name "Net-(J6-DTR)") (class "Default")
      (node (ref "C31") (pin "1") (pinfunction "1_1") (pintype "passive"))
      (node (ref "J6") (pin "1") (pinfunction "DTR_1") (pintype "passive"))
    )
    (net (code "25") (name "Net-(Q2-D)") (class "Default")
      (node (ref "Q2") (pin "3") (pinfunction "D_3") (pintype "passive"))
      (node (ref "Q3") (pin "1") (pinfunction "G_1") (pintype "passive"))
      (node (ref "R22") (pin "1") (pinfunction "P$1_1") (pintype "passive"))
    )
    (net (code "26") (name "Net-(Q3-D)") (class "Default")
      (node (ref "Q3") (pin "3") (pinfunction "D_3") (pintype "passive"))
      (node (ref "R23") (pin "2") (pinfunction "P$2_2") (pintype "passive"))
    )
    (net (code "27") (name "Net-(R4-P$1)") (class "Default")
      (node (ref "R4") (pin "1") (pinfunction "P$1_1") (pintype "passive"))
      (node (ref "R5") (pin "2") (pinfunction "P$2_2") (pintype "passive"))
      (node (ref "U2") (pin "2") (pinfunction "VPCC_2") (pintype "input"))
    )
    (net (code "28") (name "Net-(R6-P$2)") (class "Default")
      (node (ref "R6") (pin "2") (pinfunction "P$2_2") (pintype "passive"))
      (node (ref "U2") (pin "13") (pinfunction "PROG1_13") (pintype "input"))
    )
    (net (code "29") (name "Net-(R7-P$2)") (class "Default")
      (node (ref "R7") (pin "2") (pinfunction "P$2_2") (pintype "passive"))
      (node (ref "U2") (pin "12") (pinfunction "PROG3_12") (pintype "input"))
    )
    (net (code "30") (name "Net-(R8-P$2)") (class "Default")
      (node (ref "R8") (pin "2") (pinfunction "P$2_2") (pintype "passive"))
      (node (ref "U2") (pin "5") (pinfunction "THERM_5") (pintype "input"))
    )
    (net (code "31") (name "Net-(R9-P$1)") (class "Default")
      (node (ref "R9") (pin "1") (pinfunction "P$1_1") (pintype "passive"))
      (node (ref "U3") (pin "9") (pinfunction "CLRES_9") (pintype "bidirectional"))
    )
    (net (code "32") (name "Net-(R10-P$1)") (class "Default")
      (node (ref "C9") (pin "1") (pinfunction "1_1") (pintype "passive"))
      (node (ref "R10") (pin "1") (pinfunction "P$1_1") (pintype "passive"))
    )
    (net (code "33") (name "Net-(R10-P$2)") (class "Default")
      (node (ref "C10") (pin "1") (pinfunction "1_1") (pintype "passive"))
      (node (ref "R10") (pin "2") (pinfunction "P$2_2") (pintype "passive"))
      (node (ref "U3") (pin "1") (pinfunction "COMP_1") (pintype "bidirectional"))
    )
    (net (code "34") (name "Net-(R11-P$1)") (class "Default")
      (node (ref "R11") (pin "1") (pinfunction "P$1_1") (pintype "passive"))
      (node (ref "R12") (pin "2") (pinfunction "P$2_2") (pintype "passive"))
      (node (ref "U3") (pin "2") (pinfunction "FB_2") (pintype "bidirectional"))
    )
    (net (code "35") (name "Net-(R13-P$2)") (class "Default")
      (node (ref "C15") (pin "1") (pinfunction "1_1") (pintype "passive"))
      (node (ref "C16") (pin "2") (pinfunction "2_2") (pintype "passive"))
      (node (ref "R13") (pin "2") (pinfunction "P$2_2") (pintype "passive"))
      (node (ref "U4") (pin "3") (pinfunction "T-_3") (pintype "bidirectional"))
    )
    (net (code "36") (name "Net-(R14-P$2)") (class "Default")
      (node (ref "C16") (pin "1") (pinfunction "1_1") (pintype "passive"))
      (node (ref "C17") (pin "2") (pinfunction "2_2") (pintype "passive"))
      (node (ref "R14") (pin "2") (pinfunction "P$2_2") (pintype "passive"))
      (node (ref "U4") (pin "4") (pinfunction "T+_4") (pintype "bidirectional"))
    )
    (net (code "37") (name "Net-(R15-P$2)") (class "Default")
      (node (ref "C18") (pin "1") (pinfunction "1_1") (pintype "passive"))
      (node (ref "C19") (pin "2") (pinfunction "2_2") (pintype "passive"))
      (node (ref "R15") (pin "2") (pinfunction "P$2_2") (pintype "passive"))
      (node (ref "U5") (pin "3") (pinfunction "T-_3") (pintype "bidirectional"))
    )
    (net (code "38") (name "Net-(R16-P$2)") (class "Default")
      (node (ref "C19") (pin "1") (pinfunction "1_1") (pintype "passive"))
      (node (ref "C20") (pin "2") (pinfunction "2_2") (pintype "passive"))
      (node (ref "R16") (pin "2") (pinfunction "P$2_2") (pintype "passive"))
      (node (ref "U5") (pin "4") (pinfunction "T+_4") (pintype "bidirectional"))
    )
    (net (code "39") (name "Net-(R17-P$2)") (class "Default")
      (node (ref "C25") (pin "1") (pinfunction "1_1") (pintype "passive"))
      (node (ref "C26") (pin "2") (pinfunction "2_2") (pintype "passive"))
      (node (ref "R17") (pin "2") (pinfunction "P$2_2") (pintype "passive"))
      (node (ref "U6") (pin "3") (pinfunction "T-_3") (pintype "bidirectional"))
    )
    (net (code "40") (name "Net-(R18-P$2)") (class "Default")
      (node (ref "C26") (pin "1") (pinfunction "1_1") (pintype "passive"))
      (node (ref "C27") (pin "2") (pinfunction "2_2") (pintype "passive"))
      (node (ref "R18") (pin "2") (pinfunction "P$2_2") (pintype "passive"))
      (node (ref "U6") (pin "4") (pinfunction "T+_4") (pintype "bidirectional"))
    )
    (net (code "41") (name "Net-(R20-P$1)") (class "Default")
      (node (ref "R20") (pin "1") (pinfunction "P$1_1") (pintype "passive"))
      (node (ref "U7") (pin "23") (pinfunction "PC0(ADC0)_23") (pintype "bidirectional"))
    )
    (net (code "42") (name "Net-(R20-P$2)") (class "Default")
      (node (ref "D6") (pin "ANODE") (pinfunction "ANODE_ANODE") (pintype "power_in"))
      (node (ref "R20") (pin "2") (pinfunction "P$2_2") (pintype "passive"))
    )
    (net (code "43") (name "Net-(R21-P$1)") (class "Default")
      (node (ref "R21") (pin "1") (pinfunction "P$1_1") (pintype "passive"))
      (node (ref "U7") (pin "13") (pinfunction "PB1(OC1A)_13") (pintype "bidirectional"))
    )
    (net (code "44") (name "Net-(R21-P$2)") (class "Default")
      (node (ref "D7") (pin "ANODE") (pinfunction "ANODE_ANODE") (pintype "power_in"))
      (node (ref "R21") (pin "2") (pinfunction "P$2_2") (pintype "passive"))
    )
    (net (code "45") (name "Net-(U1-SW1)") (class "Default")
      (node (ref "L1") (pin "P$1") (pinfunction "P$1_P$1") (pintype "passive"))
      (node (ref "U1") (pin "4") (pinfunction "SW1_4") (pintype "bidirectional"))
    )
    (net (code "46") (name "Net-(U1-SW2)") (class "Default")
      (node (ref "L1") (pin "P$2") (pinfunction "P$2_P$2") (pintype "passive"))
      (node (ref "U1") (pin "2") (pinfunction "SW2_2") (pintype "bidirectional"))
    )
    (net (code "47") (name "Net-(U3-SS)") (class "Default")
      (node (ref "C8") (pin "1") (pinfunction "1_1") (pintype "passive"))
      (node (ref "U3") (pin "10") (pinfunction "SS_10") (pintype "bidirectional"))
    )
    (net (code "48") (name "Net-(U7-AREF)") (class "Default")
      (node (ref "C30") (pin "1") (pinfunction "1_1") (pintype "passive"))
      (node (ref "U7") (pin "20") (pinfunction "AREF_20") (pintype "bidirectional"))
    )
    (net (code "49") (name "Net-(U7-PB6(XTAL1{slash}TOSC1))") (class "Default")
      (node (ref "U7") (pin "7") (pinfunction "PB6(XTAL1/TOSC1)_7") (pintype "bidirectional"))
      (node (ref "Y1") (pin "1") (pinfunction "1_1") (pintype "passive"))
    )
    (net (code "50") (name "Net-(U7-PB7(XTAL2{slash}TOSC2))") (class "Default")
      (node (ref "U7") (pin "8") (pinfunction "PB7(XTAL2/TOSC2)_8") (pintype "bidirectional"))
      (node (ref "Y1") (pin "3") (pinfunction "3_3") (pintype "passive"))
    )
    (net (code "51") (name "Net-(U8-ANT)") (class "Default")
      (node (ref "ANT1") (pin "1") (pinfunction "1_1") (pintype "bidirectional"))
      (node (ref "U8") (pin "9") (pinfunction "ANT_9") (pintype "passive"))
    )
    (net (code "52") (name "Net-(U8-MOSI)") (class "Default")
      (node (ref "SJ2") (pin "2") (pinfunction "2_2") (pintype "passive"))
      (node (ref "U8") (pin "3") (pinfunction "MOSI_3") (pintype "input"))
    )
    (net (code "53") (name "Net-(U8-SCK)") (class "Default")
      (node (ref "SJ1") (pin "2") (pinfunction "2_2") (pintype "passive"))
      (node (ref "U8") (pin "4") (pinfunction "SCK_4") (pintype "input"))
    )
    (net (code "54") (name "Net-(U9-CLK)") (class "Default")
      (node (ref "SJ3") (pin "1") (pinfunction "1_1") (pintype "passive"))
      (node (ref "U9") (pin "6") (pinfunction "CLK_6") (pintype "bidirectional"))
    )
    (net (code "55") (name "Net-(U9-MOSI)") (class "Default")
      (node (ref "SJ4") (pin "1") (pinfunction "1_1") (pintype "passive"))
      (node (ref "U9") (pin "5") (pinfunction "MOSI_5") (pintype "bidirectional"))
    )
    (net (code "56") (name "PWR_GD") (class "Default")
      (node (ref "U2") (pin "6") (pinfunction "/PG_6") (pintype "output"))
      (node (ref "U7") (pin "19") (pinfunction "ADC6_19") (pintype "bidirectional"))
    )
    (net (code "57") (name "RF_CS") (class "Default")
      (node (ref "U7") (pin "14") (pinfunction "PB2(SS/OC1B)_14") (pintype "bidirectional"))
      (node (ref "U8") (pin "5") (pinfunction "NSS_5") (pintype "input"))
    )
    (net (code "58") (name "RF_INT") (class "Default")
      (node (ref "U7") (pin "32") (pinfunction "PD2(INT0)_32") (pintype "bidirectional"))
      (node (ref "U8") (pin "14") (pinfunction "DIO0_14") (pintype "bidirectional"))
    )
    (net (code "59") (name "RST") (class "Default")
      (node (ref "C31") (pin "2") (pinfunction "2_2") (pintype "passive"))
      (node (ref "R19") (pin "2") (pinfunction "P$2_2") (pintype "passive"))
      (node (ref "TC1") (pin "P$5") (pinfunction "PIN5_P$5") (pintype "bidirectional"))
      (node (ref "U7") (pin "29") (pinfunction "PC6(/RESET)_29") (pintype "bidirectional"))
    )
    (net (code "60") (name "RX") (class "Default")
      (node (ref "J6") (pin "3") (pinfunction "TXO_3") (pintype "passive"))
      (node (ref "U7") (pin "30") (pinfunction "PD0(RXD)_30") (pintype "bidirectional"))
    )
    (net (code "61") (name "SCK") (class "Default")
      (node (ref "SJ1") (pin "1") (pinfunction "1_1") (pintype "passive"))
      (node (ref "SJ3") (pin "2") (pinfunction "2_2") (pintype "passive"))
      (node (ref "TC1") (pin "P$3") (pinfunction "PIN3_P$3") (pintype "bidirectional"))
      (node (ref "U4") (pin "10") (pinfunction "SCK_10") (pintype "bidirectional"))
      (node (ref "U5") (pin "10") (pinfunction "SCK_10") (pintype "bidirectional"))
      (node (ref "U6") (pin "10") (pinfunction "SCK_10") (pintype "bidirectional"))
      (node (ref "U7") (pin "17") (pinfunction "PB5(SCK)_17") (pintype "bidirectional"))
    )
    (net (code "62") (name "TC1_CS") (class "Default")
      (node (ref "U4") (pin "9") (pinfunction "CS_9") (pintype "bidirectional"))
      (node (ref "U7") (pin "11") (pinfunction "PD7(AIN1)_11") (pintype "bidirectional"))
    )
    (net (code "63") (name "TC2_CS") (class "Default")
      (node (ref "U6") (pin "9") (pinfunction "CS_9") (pintype "bidirectional"))
      (node (ref "U7") (pin "10") (pinfunction "PD6(AIN0)_10") (pintype "bidirectional"))
    )
    (net (code "64") (name "TC3_CS") (class "Default")
      (node (ref "U5") (pin "9") (pinfunction "CS_9") (pintype "bidirectional"))
      (node (ref "U7") (pin "9") (pinfunction "PD5(T1)_9") (pintype "bidirectional"))
    )
    (net (code "65") (name "TX") (class "Default")
      (node (ref "J6") (pin "2") (pinfunction "RXI_2") (pintype "passive"))
      (node (ref "U7") (pin "31") (pinfunction "PD1(TXD)_31") (pintype "bidirectional"))
    )
    (net (code "66") (name "V_BAT") (class "Default")
      (node (ref "BATT1") (pin "POS_1") (pinfunction "VBAT_POS_1") (pintype "bidirectional"))
      (node (ref "BATT1") (pin "POS_2") (pinfunction "VBAT_POS_2") (pintype "bidirectional"))
      (node (ref "BATT1") (pin "POS_3") (pinfunction "VBAT_POS_3") (pintype "bidirectional"))
      (node (ref "C1") (pin "1") (pinfunction "1_1") (pintype "passive"))
      (node (ref "C5") (pin "1") (pinfunction "1_1") (pintype "passive"))
      (node (ref "C6") (pin "2") (pinfunction "2_2") (pintype "passive"))
      (node (ref "C7") (pin "1") (pinfunction "1_1") (pintype "passive"))
      (node (ref "L2") (pin "1") (pinfunction "P$1_1") (pintype "passive"))
      (node (ref "Q3") (pin "2") (pinfunction "S_2") (pintype "passive"))
      (node (ref "R22") (pin "2") (pinfunction "P$2_2") (pintype "passive"))
      (node (ref "U1") (pin "5") (pinfunction "PVIN_5") (pintype "bidirectional"))
      (node (ref "U1") (pin "6") (pinfunction "EN_6") (pintype "bidirectional"))
      (node (ref "U1") (pin "8") (pinfunction "VIN_8") (pintype "bidirectional"))
      (node (ref "U2") (pin "14") (pinfunction "VBAT1_14") (pintype "output"))
      (node (ref "U2") (pin "15") (pinfunction "VBAT2_15") (pintype "output"))
      (node (ref "U2") (pin "16") (pinfunction "VBAT3_16") (pintype "output"))
      (node (ref "U3") (pin "8") (pinfunction "VIN_8") (pintype "bidirectional"))
    )
    (net (code "67") (name "V_LOAD") (class "Default")
      (node (ref "C4") (pin "1") (pinfunction "1_1") (pintype "passive"))
      (node (ref "U2") (pin "1") (pinfunction "OUT1_1") (pintype "output"))
      (node (ref "U2") (pin "20") (pinfunction "OUT2_20") (pintype "output"))
    )
    (net (code "68") (name "V_SOLAR") (class "Default")
      (node (ref "C11") (pin "POS") (pinfunction "POS_POS") (pintype "passive"))
      (node (ref "C12") (pin "1") (pinfunction "1_1") (pintype "passive"))
      (node (ref "D4") (pin "C") (pinfunction "C_C") (pintype "passive"))
      (node (ref "R4") (pin "2") (pinfunction "P$2_2") (pintype "passive"))
      (node (ref "U2") (pin "17") (pinfunction "CE_17") (pintype "input"))
      (node (ref "U2") (pin "18") (pinfunction "IN1_18") (pintype "input"))
      (node (ref "U2") (pin "19") (pinfunction "IN2_19") (pintype "input"))
      (node (ref "U2") (pin "3") (pinfunction "SEL_3") (pintype "input"))
      (node (ref "U2") (pin "4") (pinfunction "PROG2_4") (pintype "input"))
      (node (ref "U2") (pin "9") (pinfunction "/TE_9") (pintype "input"))
    )
    (net (code "69") (name "unconnected-(J6-CTS-Pad5)") (class "Default")
      (node (ref "J6") (pin "5") (pinfunction "CTS_5") (pintype "passive"))
    )
    (net (code "70") (name "unconnected-(U2-STAT1{slash}LBO-Pad8)") (class "Default")
      (node (ref "U2") (pin "8") (pinfunction "STAT1/LBO_8") (pintype "output"))
    )
    (net (code "71") (name "unconnected-(U2-STAT2-Pad7)") (class "Default")
      (node (ref "U2") (pin "7") (pinfunction "STAT2_7") (pintype "output"))
    )
    (net (code "72") (name "unconnected-(U4-DNC-Pad6)") (class "Default")
      (node (ref "U4") (pin "6") (pinfunction "DNC_6") (pintype "bidirectional"))
    )
    (net (code "73") (name "unconnected-(U4-DRDY-Pad7)") (class "Default")
      (node (ref "U4") (pin "7") (pinfunction "DRDY_7") (pintype "bidirectional"))
    )
    (net (code "74") (name "unconnected-(U4-FAULT-Pad13)") (class "Default")
      (node (ref "U4") (pin "13") (pinfunction "FAULT_13") (pintype "bidirectional"))
    )
    (net (code "75") (name "unconnected-(U5-DNC-Pad6)") (class "Default")
      (node (ref "U5") (pin "6") (pinfunction "DNC_6") (pintype "bidirectional"))
    )
    (net (code "76") (name "unconnected-(U5-DRDY-Pad7)") (class "Default")
      (node (ref "U5") (pin "7") (pinfunction "DRDY_7") (pintype "bidirectional"))
    )
    (net (code "77") (name "unconnected-(U5-FAULT-Pad13)") (class "Default")
      (node (ref "U5") (pin "13") (pinfunction "FAULT_13") (pintype "bidirectional"))
    )
    (net (code "78") (name "unconnected-(U6-DNC-Pad6)") (class "Default")
      (node (ref "U6") (pin "6") (pinfunction "DNC_6") (pintype "bidirectional"))
    )
    (net (code "79") (name "unconnected-(U6-DRDY-Pad7)") (class "Default")
      (node (ref "U6") (pin "7") (pinfunction "DRDY_7") (pintype "bidirectional"))
    )
    (net (code "80") (name "unconnected-(U6-FAULT-Pad13)") (class "Default")
      (node (ref "U6") (pin "13") (pinfunction "FAULT_13") (pintype "bidirectional"))
    )
    (net (code "81") (name "unconnected-(U8-DIO1-Pad15)") (class "Default")
      (node (ref "U8") (pin "15") (pinfunction "DIO1_15") (pintype "bidirectional"))
    )
    (net (code "82") (name "unconnected-(U8-DIO2-Pad16)") (class "Default")
      (node (ref "U8") (pin "16") (pinfunction "DIO2_16") (pintype "bidirectional"))
    )
    (net (code "83") (name "unconnected-(U8-DIO3-Pad11)") (class "Default")
      (node (ref "U8") (pin "11") (pinfunction "DIO3_11") (pintype "bidirectional"))
    )
    (net (code "84") (name "unconnected-(U8-DIO4-Pad12)") (class "Default")
      (node (ref "U8") (pin "12") (pinfunction "DIO4_12") (pintype "bidirectional"))
    )
    (net (code "85") (name "unconnected-(U8-DIO5-Pad7)") (class "Default")
      (node (ref "U8") (pin "7") (pinfunction "DIO5_7") (pintype "bidirectional"))
    )
    (net (code "86") (name "unconnected-(U8-RESET-Pad6)") (class "Default")
      (node (ref "U8") (pin "6") (pinfunction "RESET_6") (pintype "input"))
    )
  )
)
